# microzed_sd_v0_4_9a88cbe4.net
KiCad netlist of a schematic drawn in EAGLE
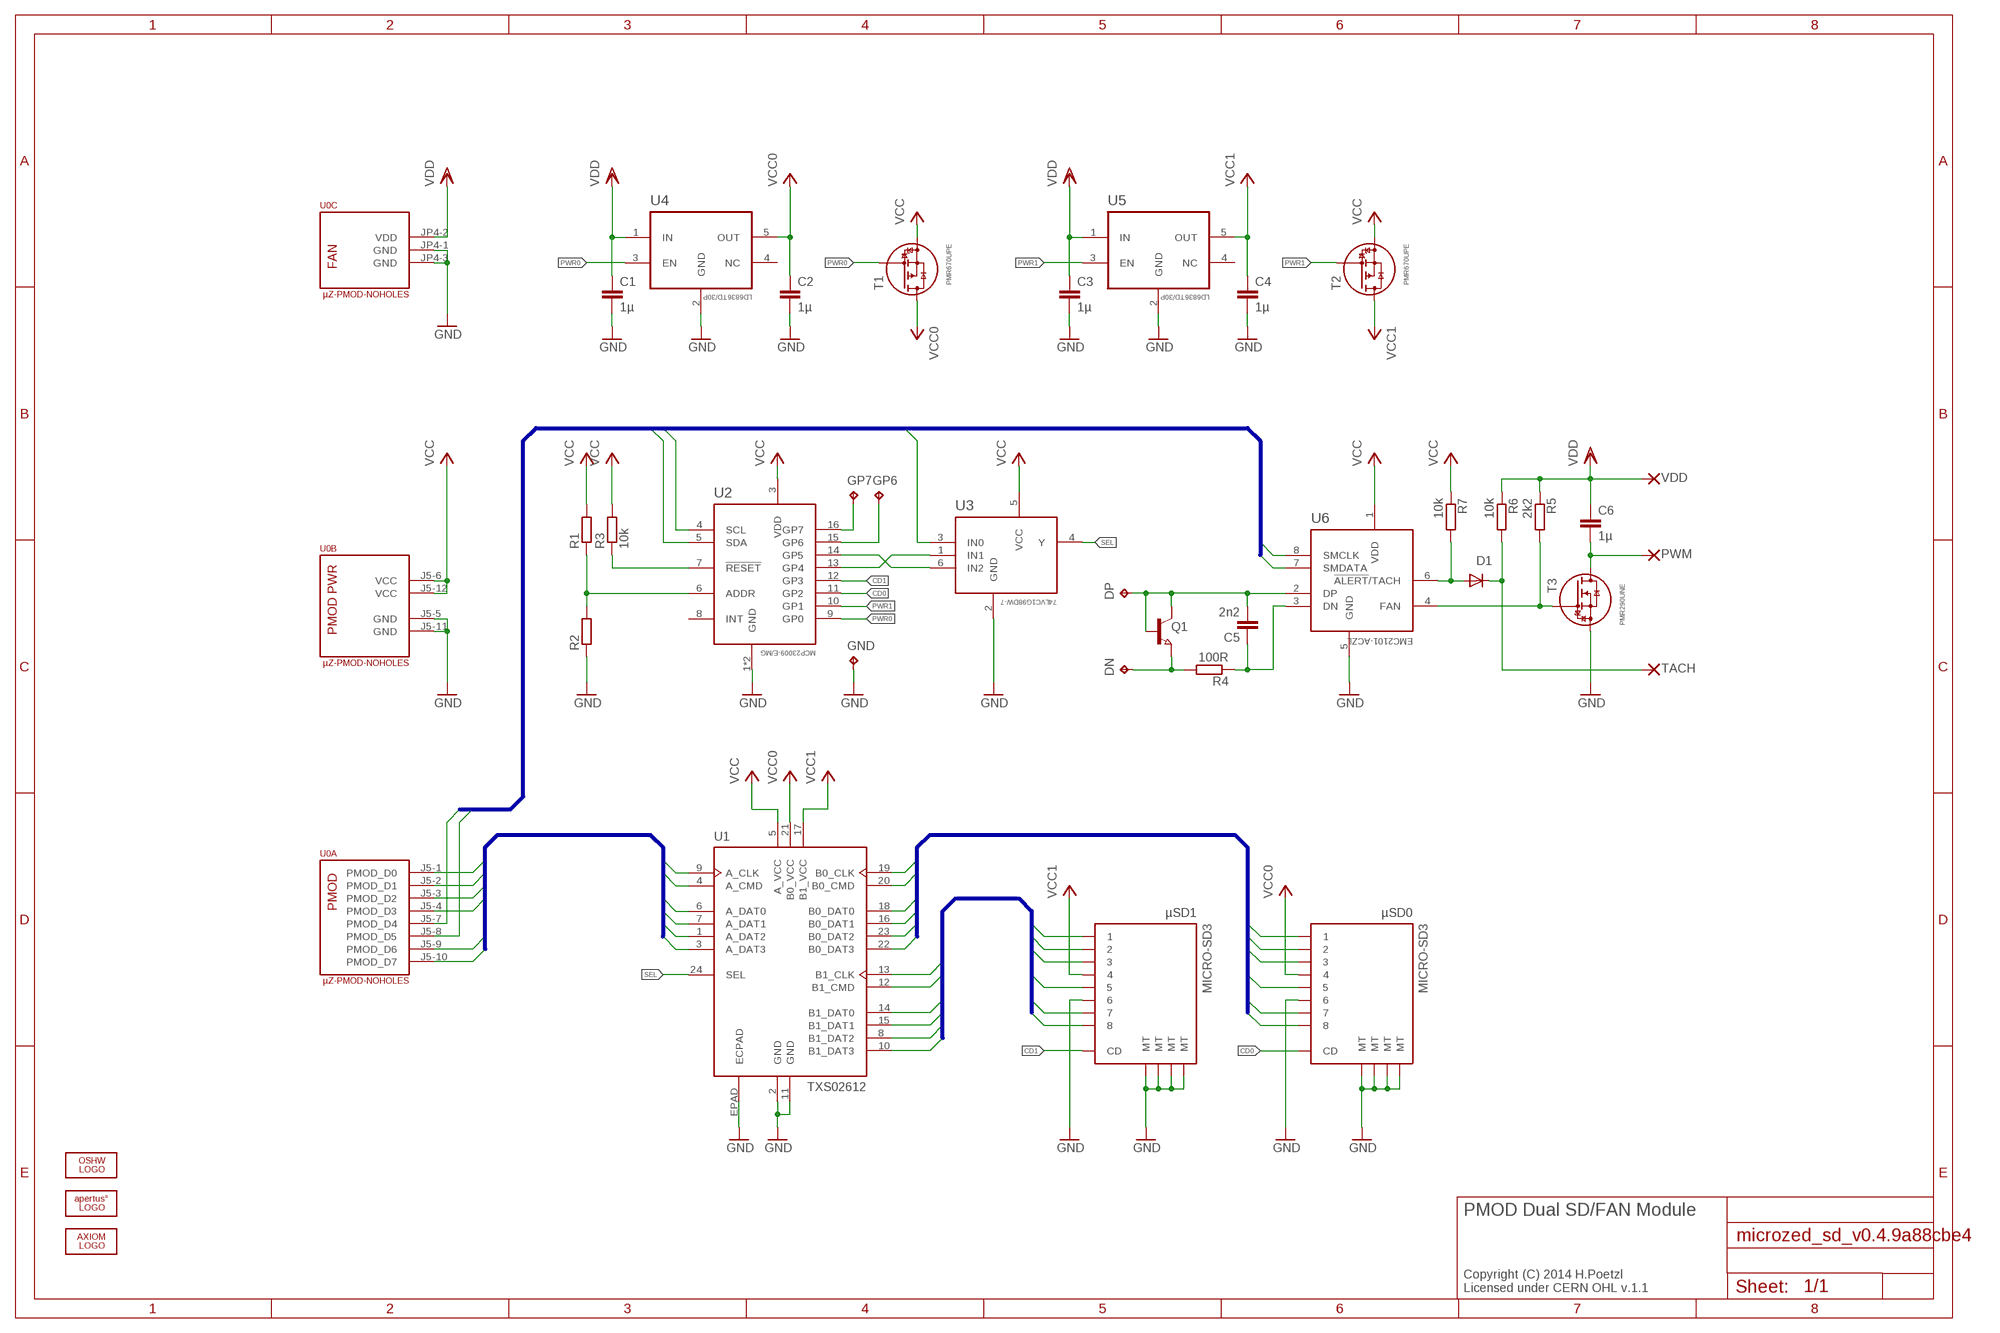
[diagram p0: schematic, sheet 1]

(export (version "E")
  (design (tool "Eeschema 10.0.6"))
  (components
    (comp (ref "C1")
      (value "1µ")
      (footprint "eagle-import:C0402K")
      (libsource (lib "eagle-import") (part "C-EUC0402K"))
    )
    (comp (ref "C2")
      (value "1µ")
      (footprint "eagle-import:C0402K")
      (libsource (lib "eagle-import") (part "C-EUC0402K"))
    )
    (comp (ref "C3")
      (value "1µ")
      (footprint "eagle-import:C0402K")
      (libsource (lib "eagle-import") (part "C-EUC0402K"))
    )
    (comp (ref "C4")
      (value "1µ")
      (footprint "eagle-import:C0402K")
      (libsource (lib "eagle-import") (part "C-EUC0402K"))
    )
    (comp (ref "C5")
      (value "2n2")
      (footprint "eagle-import:C0402K")
      (libsource (lib "eagle-import") (part "C-EUC0402K"))
    )
    (comp (ref "C6")
      (value "1µ")
      (footprint "eagle-import:C0402K")
      (libsource (lib "eagle-import") (part "C-EUC0402K"))
    )
    (comp (ref "D1")
      (value "DIODE-MICROMELF-W")
      (footprint "eagle-import:MICROMELF-W")
      (libsource (lib "eagle-import") (part "DIODE-MICROMELF-W"))
    )
    (comp (ref "DN")
      (value "TPTP20R")
      (footprint "eagle-import:TP20R")
      (libsource (lib "eagle-import") (part "TPTP20R"))
    )
    (comp (ref "DP")
      (value "TPTP20R")
      (footprint "eagle-import:TP20R")
      (libsource (lib "eagle-import") (part "TPTP20R"))
    )
    (comp (ref "GND")
      (value "TPTP20R")
      (footprint "eagle-import:TP20R")
      (libsource (lib "eagle-import") (part "TPTP20R"))
    )
    (comp (ref "GP6")
      (value "TPTP20R")
      (footprint "eagle-import:TP20R")
      (libsource (lib "eagle-import") (part "TPTP20R"))
    )
    (comp (ref "GP7")
      (value "TPTP20R")
      (footprint "eagle-import:TP20R")
      (libsource (lib "eagle-import") (part "TPTP20R"))
    )
    (comp (ref "LOGO1")
      (value "OSHW_LOGO_FILLX0100-NT")
      (footprint "eagle-import:OSHW_FILLX100_NOTEXT")
      (libsource (lib "eagle-import") (part "OSHW_LOGO_FILLX0100-NT"))
    )
    (comp (ref "PWM")
      (value "WIREPAD2,15/1,0")
      (footprint "eagle-import:2,15_1,0")
      (libsource (lib "eagle-import") (part "WIREPAD2,15/1,0"))
    )
    (comp (ref "Q1")
      (value "NPN-TRANSISTOR_SOT23")
      (footprint "eagle-import:SOT23")
      (libsource (lib "eagle-import") (part "NPN-TRANSISTOR_SOT23"))
    )
    (comp (ref "R1")
      (value "R-EU_R0603")
      (footprint "eagle-import:R0603")
      (libsource (lib "eagle-import") (part "R-EU_R0603"))
    )
    (comp (ref "R2")
      (value "R-EU_R0603")
      (footprint "eagle-import:R0603")
      (libsource (lib "eagle-import") (part "R-EU_R0603"))
    )
    (comp (ref "R3")
      (value "10k")
      (footprint "eagle-import:R0603")
      (libsource (lib "eagle-import") (part "R-EU_R0603"))
    )
    (comp (ref "R4")
      (value "100R")
      (footprint "eagle-import:R0402")
      (libsource (lib "eagle-import") (part "R-EU_R0402"))
    )
    (comp (ref "R5")
      (value "2k2")
      (footprint "eagle-import:R0402")
      (libsource (lib "eagle-import") (part "R-EU_R0402"))
    )
    (comp (ref "R6")
      (value "10k")
      (footprint "eagle-import:R0402")
      (libsource (lib "eagle-import") (part "R-EU_R0402"))
    )
    (comp (ref "R7")
      (value "10k")
      (footprint "eagle-import:R0402")
      (libsource (lib "eagle-import") (part "R-EU_R0402"))
    )
    (comp (ref "T1")
      (value "PMR670UPE")
      (footprint "eagle-import:SOT416")
      (libsource (lib "eagle-import") (part "PMR670UPE"))
    )
    (comp (ref "T2")
      (value "PMR670UPE")
      (footprint "eagle-import:SOT416")
      (libsource (lib "eagle-import") (part "PMR670UPE"))
    )
    (comp (ref "T3")
      (value "PMR290UNE")
      (footprint "eagle-import:SOT416")
      (libsource (lib "eagle-import") (part "PMR290UNE"))
    )
    (comp (ref "TACH")
      (value "WIREPAD2,15/1,0")
      (footprint "eagle-import:2,15_1,0")
      (libsource (lib "eagle-import") (part "WIREPAD2,15/1,0"))
    )
    (comp (ref "U$1")
      (value "APERTUS_LOGO334X100")
      (footprint "eagle-import:APERTUS_LOGO_334X100")
      (libsource (lib "eagle-import") (part "APERTUS_LOGO334X100"))
    )
    (comp (ref "U$13")
      (value "AXIOM_LOGO525X80")
      (footprint "eagle-import:AXIOM_LOGO_525X80")
      (libsource (lib "eagle-import") (part "AXIOM_LOGO525X80"))
    )
    (comp (ref "U0")
      (value "µZ-PMOD-NOHOLES")
      (footprint "eagle-import:µZ-TOP-NOHOLES")
      (libsource (lib "eagle-import") (part "µZ-PMOD-NOHOLES"))
    )
    (comp (ref "U1")
      (value "TXS02612")
      (footprint "eagle-import:S-PWQFN-N24")
      (libsource (lib "eagle-import") (part "TXS02612"))
    )
    (comp (ref "U2")
      (value "MCP23009-E/MG")
      (footprint "eagle-import:QFN50P300X300X80-17N")
      (libsource (lib "eagle-import") (part "MCP23009-E/MG"))
    )
    (comp (ref "U3")
      (value "74LVC1G98DW-7")
      (footprint "eagle-import:SOT65P210X110-6N")
      (libsource (lib "eagle-import") (part "74LVC1G98DW-7"))
    )
    (comp (ref "U4")
      (value "LD6836TD/30P")
      (footprint "eagle-import:SOT95P275X110-5N")
      (libsource (lib "eagle-import") (part "LD6836TD/30P"))
    )
    (comp (ref "U5")
      (value "LD6836TD/30P")
      (footprint "eagle-import:SOT95P275X110-5N")
      (libsource (lib "eagle-import") (part "LD6836TD/30P"))
    )
    (comp (ref "U6")
      (value "EMC2101-ACZL")
      (footprint "eagle-import:SOP65P490X110-8N")
      (fields (field (name "MPN") "EMC2101-ACZL-TR "))
      (libsource (lib "eagle-import") (part "EMC2101-ACZL"))
    )
    (comp (ref "VDD")
      (value "WIREPAD2,15/1,0")
      (footprint "eagle-import:2,15_1,0")
      (libsource (lib "eagle-import") (part "WIREPAD2,15/1,0"))
    )
    (comp (ref "µSD0")
      (value "MICRO-SD3")
      (footprint "eagle-import:TF-MICRO-SD_PP3")
      (libsource (lib "eagle-import") (part "MICRO-SD3"))
    )
    (comp (ref "µSD1")
      (value "MICRO-SD3")
      (footprint "eagle-import:TF-MICRO-SD_PP3")
      (libsource (lib "eagle-import") (part "MICRO-SD3"))
    )
  )
  (nets
    (net (code "1") (name "/A_CLK") (class "Default")
      (node (ref "U0") (pin "J5-4") (pinfunction "PMOD_D3_J5-4") (pintype "bidirectional"))
      (node (ref "U1") (pin "9") (pinfunction "A_CLK_9") (pintype "input"))
    )
    (net (code "2") (name "/A_CMD") (class "Default")
      (node (ref "U0") (pin "J5-3") (pinfunction "PMOD_D2_J5-3") (pintype "bidirectional"))
      (node (ref "U1") (pin "4") (pinfunction "A_CMD_4") (pintype "bidirectional"))
    )
    (net (code "3") (name "/A_DAT0") (class "Default")
      (node (ref "U0") (pin "J5-2") (pinfunction "PMOD_D1_J5-2") (pintype "bidirectional"))
      (node (ref "U1") (pin "6") (pinfunction "A_DAT0_6") (pintype "bidirectional"))
    )
    (net (code "4") (name "/A_DAT1") (class "Default")
      (node (ref "U0") (pin "J5-1") (pinfunction "PMOD_D0_J5-1") (pintype "bidirectional"))
      (node (ref "U1") (pin "7") (pinfunction "A_DAT1_7") (pintype "bidirectional"))
    )
    (net (code "5") (name "/A_DAT2") (class "Default")
      (node (ref "U0") (pin "J5-9") (pinfunction "PMOD_D6_J5-9") (pintype "bidirectional"))
      (node (ref "U1") (pin "1") (pinfunction "A_DAT2_1") (pintype "bidirectional"))
    )
    (net (code "6") (name "/A_DAT3") (class "Default")
      (node (ref "U0") (pin "J5-10") (pinfunction "PMOD_D7_J5-10") (pintype "bidirectional"))
      (node (ref "U1") (pin "3") (pinfunction "A_DAT3_3") (pintype "bidirectional"))
    )
    (net (code "7") (name "/B0_CLK") (class "Default")
      (node (ref "U1") (pin "19") (pinfunction "B0_CLK_19") (pintype "output"))
      (node (ref "µSD0") (pin "5") (pinfunction "5_5") (pintype "bidirectional"))
    )
    (net (code "8") (name "/B0_CMD") (class "Default")
      (node (ref "U1") (pin "20") (pinfunction "B0_CMD_20") (pintype "bidirectional"))
      (node (ref "µSD0") (pin "3") (pinfunction "3_3") (pintype "bidirectional"))
    )
    (net (code "9") (name "/B0_DAT0") (class "Default")
      (node (ref "U1") (pin "18") (pinfunction "B0_DAT0_18") (pintype "bidirectional"))
      (node (ref "µSD0") (pin "7") (pinfunction "7_7") (pintype "bidirectional"))
    )
    (net (code "10") (name "/B0_DAT1") (class "Default")
      (node (ref "U1") (pin "16") (pinfunction "B0_DAT1_16") (pintype "bidirectional"))
      (node (ref "µSD0") (pin "8") (pinfunction "8_8") (pintype "bidirectional"))
    )
    (net (code "11") (name "/B0_DAT2") (class "Default")
      (node (ref "U1") (pin "23") (pinfunction "B0_DAT2_23") (pintype "bidirectional"))
      (node (ref "µSD0") (pin "1") (pinfunction "1_1") (pintype "bidirectional"))
    )
    (net (code "12") (name "/B0_DAT3") (class "Default")
      (node (ref "U1") (pin "22") (pinfunction "B0_DAT3_22") (pintype "bidirectional"))
      (node (ref "µSD0") (pin "2") (pinfunction "2_2") (pintype "bidirectional"))
    )
    (net (code "13") (name "/B1_CLK") (class "Default")
      (node (ref "U1") (pin "13") (pinfunction "B1_CLK_13") (pintype "output"))
      (node (ref "µSD1") (pin "5") (pinfunction "5_5") (pintype "bidirectional"))
    )
    (net (code "14") (name "/B1_CMD") (class "Default")
      (node (ref "U1") (pin "12") (pinfunction "B1_CMD_12") (pintype "bidirectional"))
      (node (ref "µSD1") (pin "3") (pinfunction "3_3") (pintype "bidirectional"))
    )
    (net (code "15") (name "/B1_DAT0") (class "Default")
      (node (ref "U1") (pin "14") (pinfunction "B1_DAT0_14") (pintype "bidirectional"))
      (node (ref "µSD1") (pin "7") (pinfunction "7_7") (pintype "bidirectional"))
    )
    (net (code "16") (name "/B1_DAT1") (class "Default")
      (node (ref "U1") (pin "15") (pinfunction "B1_DAT1_15") (pintype "bidirectional"))
      (node (ref "µSD1") (pin "8") (pinfunction "8_8") (pintype "bidirectional"))
    )
    (net (code "17") (name "/B1_DAT2") (class "Default")
      (node (ref "U1") (pin "8") (pinfunction "B1_DAT2_8") (pintype "bidirectional"))
      (node (ref "µSD1") (pin "1") (pinfunction "1_1") (pintype "bidirectional"))
    )
    (net (code "18") (name "/B1_DAT3") (class "Default")
      (node (ref "U1") (pin "10") (pinfunction "B1_DAT3_10") (pintype "bidirectional"))
      (node (ref "µSD1") (pin "2") (pinfunction "2_2") (pintype "bidirectional"))
    )
    (net (code "19") (name "/SCL") (class "Default")
      (node (ref "U0") (pin "J5-7") (pinfunction "PMOD_D4_J5-7") (pintype "bidirectional"))
      (node (ref "U2") (pin "4") (pinfunction "SCL_4") (pintype "input"))
      (node (ref "U6") (pin "8") (pinfunction "SMCLK_8") (pintype "input"))
    )
    (net (code "20") (name "/SDA") (class "Default")
      (node (ref "U0") (pin "J5-8") (pinfunction "PMOD_D5_J5-8") (pintype "bidirectional"))
      (node (ref "U2") (pin "5") (pinfunction "SDA_5") (pintype "bidirectional"))
      (node (ref "U3") (pin "3") (pinfunction "IN0_3") (pintype "input"))
      (node (ref "U6") (pin "7") (pinfunction "SMDATA_7") (pintype "bidirectional"))
    )
    (net (code "21") (name "CD0") (class "Default")
      (node (ref "U2") (pin "11") (pinfunction "GP2_11") (pintype "bidirectional"))
      (node (ref "µSD0") (pin "CD") (pinfunction "CD_CD") (pintype "bidirectional"))
    )
    (net (code "22") (name "CD1") (class "Default")
      (node (ref "U2") (pin "12") (pinfunction "GP3_12") (pintype "bidirectional"))
      (node (ref "µSD1") (pin "CD") (pinfunction "CD_CD") (pintype "bidirectional"))
    )
    (net (code "23") (name "GND") (class "Default")
      (node (ref "C1") (pin "2") (pinfunction "2_2") (pintype "passive"))
      (node (ref "C2") (pin "2") (pinfunction "2_2") (pintype "passive"))
      (node (ref "C3") (pin "2") (pinfunction "2_2") (pintype "passive"))
      (node (ref "C4") (pin "2") (pinfunction "2_2") (pintype "passive"))
      (node (ref "GND") (pin "TP") (pinfunction "TP_TP") (pintype "input"))
      (node (ref "R2") (pin "1") (pinfunction "1_1") (pintype "passive"))
      (node (ref "T3") (pin "2") (pinfunction "S_2") (pintype "passive"))
      (node (ref "U0") (pin "J5-11") (pinfunction "GND_J5-11") (pintype "power_in"))
      (node (ref "U0") (pin "J5-5") (pinfunction "GND_J5-5") (pintype "power_in"))
      (node (ref "U0") (pin "JP4-1") (pinfunction "GND_JP4-1") (pintype "power_in"))
      (node (ref "U0") (pin "JP4-3") (pinfunction "GND_JP4-3") (pintype "power_in"))
      (node (ref "U1") (pin "11") (pinfunction "GND_11") (pintype "power_in"))
      (node (ref "U1") (pin "2") (pinfunction "GND_2") (pintype "power_in"))
      (node (ref "U1") (pin "EPAD") (pinfunction "ECPAD_EPAD") (pintype "power_in"))
      (node (ref "U2") (pin "1") (pinfunction "GND_1") (pintype "power_in"))
      (node (ref "U2") (pin "17") (pinfunction "GND_17") (pintype "power_in"))
      (node (ref "U3") (pin "2") (pinfunction "GND_2") (pintype "passive"))
      (node (ref "U4") (pin "2") (pinfunction "GND_2") (pintype "passive"))
      (node (ref "U5") (pin "2") (pinfunction "GND_2") (pintype "passive"))
      (node (ref "U6") (pin "5") (pinfunction "GND_5") (pintype "power_in"))
      (node (ref "µSD0") (pin "6") (pinfunction "6_6") (pintype "bidirectional"))
      (node (ref "µSD0") (pin "MT1") (pinfunction "MT_MT1") (pintype "power_in"))
      (node (ref "µSD0") (pin "MT2") (pinfunction "MT_MT2") (pintype "power_in"))
      (node (ref "µSD0") (pin "MT3") (pinfunction "MT_MT3") (pintype "power_in"))
      (node (ref "µSD0") (pin "MT4") (pinfunction "MT_MT4") (pintype "power_in"))
      (node (ref "µSD1") (pin "6") (pinfunction "6_6") (pintype "bidirectional"))
      (node (ref "µSD1") (pin "MT1") (pinfunction "MT_MT1") (pintype "power_in"))
      (node (ref "µSD1") (pin "MT2") (pinfunction "MT_MT2") (pintype "power_in"))
      (node (ref "µSD1") (pin "MT3") (pinfunction "MT_MT3") (pintype "power_in"))
      (node (ref "µSD1") (pin "MT4") (pinfunction "MT_MT4") (pintype "power_in"))
    )
    (net (code "24") (name "Net-(PWM-P)") (class "Default")
      (node (ref "C6") (pin "2") (pinfunction "2_2") (pintype "passive"))
      (node (ref "PWM") (pin "1") (pinfunction "P_1") (pintype "passive"))
      (node (ref "T3") (pin "3") (pinfunction "D_3") (pintype "passive"))
    )
    (net (code "25") (name "Net-(Q1-B)") (class "Default")
      (node (ref "C5") (pin "2") (pinfunction "2_2") (pintype "passive"))
      (node (ref "DP") (pin "TP") (pinfunction "TP_TP") (pintype "input"))
      (node (ref "Q1") (pin "1") (pinfunction "B_1") (pintype "passive"))
      (node (ref "Q1") (pin "3") (pinfunction "C_3") (pintype "passive"))
      (node (ref "U6") (pin "2") (pinfunction "DP_2") (pintype "passive"))
    )
    (net (code "26") (name "Net-(Q1-E)") (class "Default")
      (node (ref "DN") (pin "TP") (pinfunction "TP_TP") (pintype "input"))
      (node (ref "Q1") (pin "2") (pinfunction "E_2") (pintype "passive"))
      (node (ref "R4") (pin "2") (pinfunction "2_2") (pintype "passive"))
    )
    (net (code "27") (name "Net-(T3-G)") (class "Default")
      (node (ref "R5") (pin "2") (pinfunction "2_2") (pintype "passive"))
      (node (ref "T3") (pin "1") (pinfunction "G_1") (pintype "passive"))
      (node (ref "U6") (pin "4") (pinfunction "FAN_4") (pintype "output"))
    )
    (net (code "28") (name "Net-(TACH-P)") (class "Default")
      (node (ref "D1") (pin "C") (pinfunction "C_C") (pintype "passive"))
      (node (ref "R6") (pin "2") (pinfunction "2_2") (pintype "passive"))
      (node (ref "TACH") (pin "1") (pinfunction "P_1") (pintype "passive"))
    )
    (net (code "29") (name "Net-(U2-ADDR)") (class "Default")
      (node (ref "R1") (pin "1") (pinfunction "1_1") (pintype "passive"))
      (node (ref "R2") (pin "2") (pinfunction "2_2") (pintype "passive"))
      (node (ref "U2") (pin "6") (pinfunction "ADDR_6") (pintype "input"))
    )
    (net (code "30") (name "Net-(U2-GP4)") (class "Default")
      (node (ref "U2") (pin "13") (pinfunction "GP4_13") (pintype "bidirectional"))
      (node (ref "U3") (pin "1") (pinfunction "IN1_1") (pintype "input"))
    )
    (net (code "31") (name "Net-(U2-GP5)") (class "Default")
      (node (ref "U2") (pin "14") (pinfunction "GP5_14") (pintype "bidirectional"))
      (node (ref "U3") (pin "6") (pinfunction "IN2_6") (pintype "input"))
    )
    (net (code "32") (name "Net-(U2-GP6)") (class "Default")
      (node (ref "GP6") (pin "TP") (pinfunction "TP_TP") (pintype "input"))
      (node (ref "U2") (pin "15") (pinfunction "GP6_15") (pintype "bidirectional"))
    )
    (net (code "33") (name "Net-(U2-GP7)") (class "Default")
      (node (ref "GP7") (pin "TP") (pinfunction "TP_TP") (pintype "input"))
      (node (ref "U2") (pin "16") (pinfunction "GP7_16") (pintype "bidirectional"))
    )
    (net (code "34") (name "Net-(U2-~{RESET})") (class "Default")
      (node (ref "R3") (pin "1") (pinfunction "1_1") (pintype "passive"))
      (node (ref "U2") (pin "7") (pinfunction "~{RESET}_7") (pintype "input"))
    )
    (net (code "35") (name "Net-(U6-DN)") (class "Default")
      (node (ref "C5") (pin "1") (pinfunction "1_1") (pintype "passive"))
      (node (ref "R4") (pin "1") (pinfunction "1_1") (pintype "passive"))
      (node (ref "U6") (pin "3") (pinfunction "DN_3") (pintype "passive"))
    )
    (net (code "36") (name "Net-(U6-~{ALERT}{slash}TACH)") (class "Default")
      (node (ref "D1") (pin "A") (pinfunction "A_A") (pintype "passive"))
      (node (ref "R7") (pin "2") (pinfunction "2_2") (pintype "passive"))
      (node (ref "U6") (pin "6") (pinfunction "~{ALERT}/TACH_6") (pintype "bidirectional"))
    )
    (net (code "37") (name "PWR0") (class "Default")
      (node (ref "T1") (pin "1") (pinfunction "G_1") (pintype "passive"))
      (node (ref "U2") (pin "9") (pinfunction "GP0_9") (pintype "bidirectional"))
      (node (ref "U4") (pin "3") (pinfunction "EN_3") (pintype "input"))
    )
    (net (code "38") (name "PWR1") (class "Default")
      (node (ref "T2") (pin "1") (pinfunction "G_1") (pintype "passive"))
      (node (ref "U2") (pin "10") (pinfunction "GP1_10") (pintype "bidirectional"))
      (node (ref "U5") (pin "3") (pinfunction "EN_3") (pintype "input"))
    )
    (net (code "39") (name "SEL") (class "Default")
      (node (ref "U1") (pin "24") (pinfunction "SEL_24") (pintype "input"))
      (node (ref "U3") (pin "4") (pinfunction "Y_4") (pintype "output"))
    )
    (net (code "40") (name "VCC") (class "Default")
      (node (ref "R1") (pin "2") (pinfunction "2_2") (pintype "passive"))
      (node (ref "R3") (pin "2") (pinfunction "2_2") (pintype "passive"))
      (node (ref "R7") (pin "1") (pinfunction "1_1") (pintype "passive"))
      (node (ref "T1") (pin "2") (pinfunction "S_2") (pintype "passive"))
      (node (ref "T2") (pin "2") (pinfunction "S_2") (pintype "passive"))
      (node (ref "U0") (pin "J5-12") (pinfunction "VCC_J5-12") (pintype "power_in"))
      (node (ref "U0") (pin "J5-6") (pinfunction "VCC_J5-6") (pintype "power_in"))
      (node (ref "U1") (pin "5") (pinfunction "A_VCC_5") (pintype "power_in"))
      (node (ref "U2") (pin "3") (pinfunction "VDD_3") (pintype "power_in"))
      (node (ref "U3") (pin "5") (pinfunction "VCC_5") (pintype "power_in"))
      (node (ref "U6") (pin "1") (pinfunction "VDD_1") (pintype "power_in"))
    )
    (net (code "41") (name "VCC0") (class "Default")
      (node (ref "C2") (pin "1") (pinfunction "1_1") (pintype "passive"))
      (node (ref "T1") (pin "3") (pinfunction "D_3") (pintype "passive"))
      (node (ref "U1") (pin "21") (pinfunction "B0_VCC_21") (pintype "power_in"))
      (node (ref "U4") (pin "5") (pinfunction "OUT_5") (pintype "output"))
      (node (ref "µSD0") (pin "4") (pinfunction "4_4") (pintype "bidirectional"))
    )
    (net (code "42") (name "VCC1") (class "Default")
      (node (ref "C4") (pin "1") (pinfunction "1_1") (pintype "passive"))
      (node (ref "T2") (pin "3") (pinfunction "D_3") (pintype "passive"))
      (node (ref "U1") (pin "17") (pinfunction "B1_VCC_17") (pintype "power_in"))
      (node (ref "U5") (pin "5") (pinfunction "OUT_5") (pintype "output"))
      (node (ref "µSD1") (pin "4") (pinfunction "4_4") (pintype "bidirectional"))
    )
    (net (code "43") (name "VDD") (class "Default")
      (node (ref "C1") (pin "1") (pinfunction "1_1") (pintype "passive"))
      (node (ref "C3") (pin "1") (pinfunction "1_1") (pintype "passive"))
      (node (ref "C6") (pin "1") (pinfunction "1_1") (pintype "passive"))
      (node (ref "R5") (pin "1") (pinfunction "1_1") (pintype "passive"))
      (node (ref "R6") (pin "1") (pinfunction "1_1") (pintype "passive"))
      (node (ref "U0") (pin "JP4-2") (pinfunction "VDD_JP4-2") (pintype "power_in"))
      (node (ref "U4") (pin "1") (pinfunction "IN_1") (pintype "input"))
      (node (ref "U5") (pin "1") (pinfunction "IN_1") (pintype "input"))
      (node (ref "VDD") (pin "1") (pinfunction "P_1") (pintype "passive"))
    )
    (net (code "44") (name "unconnected-(U2-INT-Pad8)") (class "Default")
      (node (ref "U2") (pin "8") (pinfunction "INT_8") (pintype "output"))
    )
    (net (code "45") (name "unconnected-(U4-NC-Pad4)") (class "Default")
      (node (ref "U4") (pin "4") (pinfunction "NC_4") (pintype "no_connect"))
    )
    (net (code "46") (name "unconnected-(U5-NC-Pad4)") (class "Default")
      (node (ref "U5") (pin "4") (pinfunction "NC_4") (pintype "no_connect"))
    )
  )
)
